# BPSensor_Board.net
KiCad netlist of a schematic drawn in Altium Designer
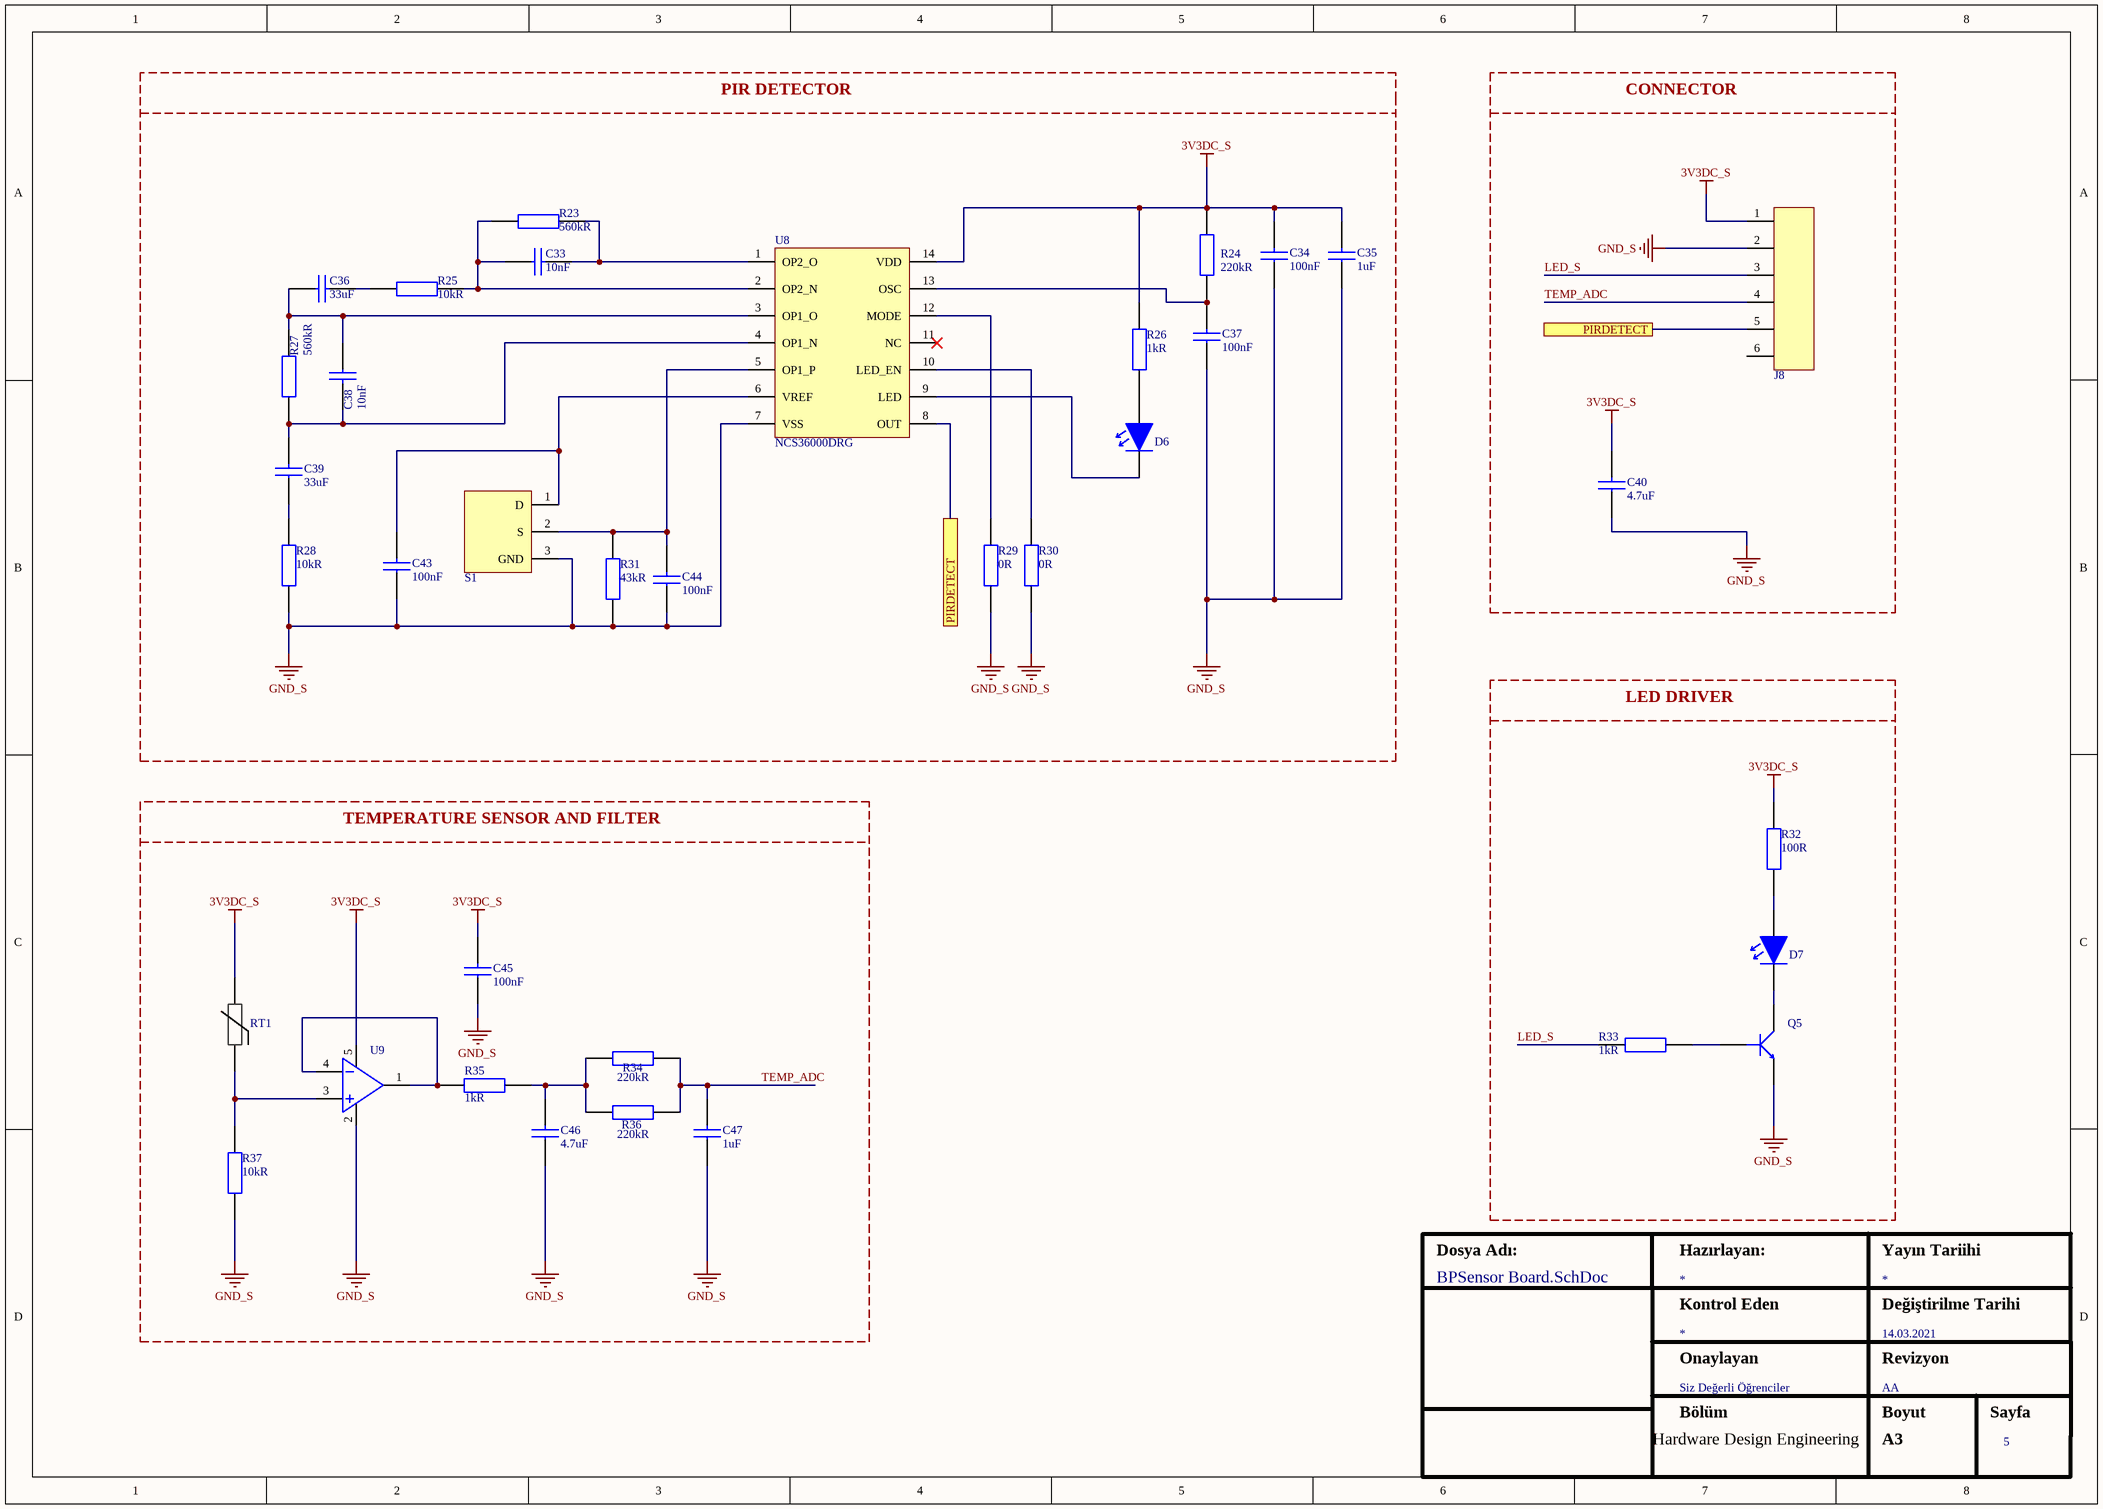
[diagram p0: BPSensor Board.SchDoc]

(export (version "E")
  (design (tool "Eeschema 10.0.6"))
  (components
    (comp (ref "C33")
      (value "0603B103K160CT")
      (footprint "CAP_0603")
      (description "CAP CER 10nF %10 0603")
      (fields
        (field (name "MANUFACTURER") "Walsin Technologies")
        (field (name "TOLERANCE") "10%")
        (field (name "CAPACITANCE") "10nF")
        (field (name "DESIGNED BY") "BERK")
      )
      (libsource (lib "UDEMY_Library") (part "CAP CER 10nF 0603"))
    )
    (comp (ref "C34")
      (value "C0603C104K5RACTU")
      (footprint "CAP_0603")
      (description "CAP CER 100nF %10 0603 SMD")
      (fields
        (field (name "MANUFACTURER") "KEMET")
        (field (name "TOLERANCE") "10%")
        (field (name "CAPACITANCE") "100nF")
        (field (name "DESIGNED BY") "BERK")
      )
      (libsource (lib "UDEMY_Library") (part "CAP CER 100nF 0603"))
    )
    (comp (ref "C35")
      (value "CL21B105KBFNNNE")
      (footprint "CAP_0805")
      (description "CAP CER 1uF %10 0805")
      (fields
        (field (name "MANUFACTURER") "Samsung")
        (field (name "TOLERANCE") "10%")
        (field (name "CAPACITANCE") "1uF")
        (field (name "DESIGNED BY") "BERK")
      )
      (libsource (lib "UDEMY_Library") (part "CAP CER 1uF 0805"))
    )
    (comp (ref "C36")
      (value "C3216X5R1E336M160AC")
      (footprint "CAP_1206")
      (description "CAP CER 33uF %20 1206 SMD")
      (fields
        (field (name "MANUFACTURER") "TDK")
        (field (name "TOLERANCE") "20%")
        (field (name "CAPACITANCE") "33uF")
        (field (name "DESIGNED BY") "BERK")
      )
      (libsource (lib "UDEMY_Library") (part "CAP CER 33uF 1206"))
    )
    (comp (ref "C37")
      (value "C0603C104K5RACTU")
      (footprint "CAP_0603")
      (description "CAP CER 100nF %10 0603 SMD")
      (fields
        (field (name "MANUFACTURER") "KEMET")
        (field (name "TOLERANCE") "10%")
        (field (name "CAPACITANCE") "100nF")
        (field (name "DESIGNED BY") "BERK")
      )
      (libsource (lib "UDEMY_Library") (part "CAP CER 100nF 0603"))
    )
    (comp (ref "C38")
      (value "0603B103K160CT")
      (footprint "CAP_0603")
      (description "CAP CER 10nF %10 0603")
      (fields
        (field (name "MANUFACTURER") "Walsin Technologies")
        (field (name "TOLERANCE") "10%")
        (field (name "CAPACITANCE") "10nF")
        (field (name "DESIGNED BY") "BERK")
      )
      (libsource (lib "UDEMY_Library") (part "CAP CER 10nF 0603"))
    )
    (comp (ref "C39")
      (value "C3216X5R1E336M160AC")
      (footprint "CAP_1206")
      (description "CAP CER 33uF %20 1206 SMD")
      (fields
        (field (name "MANUFACTURER") "TDK")
        (field (name "TOLERANCE") "20%")
        (field (name "CAPACITANCE") "33uF")
        (field (name "DESIGNED BY") "BERK")
      )
      (libsource (lib "UDEMY_Library") (part "CAP CER 33uF 1206"))
    )
    (comp (ref "C40")
      (value "CL21A475KAQNNNE")
      (footprint "CAP_0805")
      (description "CAP CER 4.7uF %10 0805")
      (fields
        (field (name "MANUFACTURER") "Samsung")
        (field (name "TOLERANCE") "10%")
        (field (name "CAPACITANCE") "4.7uF")
        (field (name "DESIGNED BY") "BERK")
      )
      (libsource (lib "UDEMY_Library") (part "CAP CER 4.7uF 0805"))
    )
    (comp (ref "C43")
      (value "C0603C104K5RACTU")
      (footprint "CAP_0603")
      (description "CAP CER 100nF %10 0603 SMD")
      (fields
        (field (name "MANUFACTURER") "KEMET")
        (field (name "TOLERANCE") "10%")
        (field (name "CAPACITANCE") "100nF")
        (field (name "DESIGNED BY") "BERK")
      )
      (libsource (lib "UDEMY_Library") (part "CAP CER 100nF 0603"))
    )
    (comp (ref "C44")
      (value "C0603C104K5RACTU")
      (footprint "CAP_0603")
      (description "CAP CER 100nF %10 0603 SMD")
      (fields
        (field (name "MANUFACTURER") "KEMET")
        (field (name "TOLERANCE") "10%")
        (field (name "CAPACITANCE") "100nF")
        (field (name "DESIGNED BY") "BERK")
      )
      (libsource (lib "UDEMY_Library") (part "CAP CER 100nF 0603"))
    )
    (comp (ref "C45")
      (value "C0603C104K5RACTU")
      (footprint "CAP_0603")
      (description "CAP CER 100nF %10 0603 SMD")
      (fields
        (field (name "MANUFACTURER") "KEMET")
        (field (name "TOLERANCE") "10%")
        (field (name "CAPACITANCE") "100nF")
        (field (name "DESIGNED BY") "BERK")
      )
      (libsource (lib "UDEMY_Library") (part "CAP CER 100nF 0603"))
    )
    (comp (ref "C46")
      (value "CL21A475KAQNNNE")
      (footprint "CAP_0805")
      (description "CAP CER 4.7uF %10 0805")
      (fields
        (field (name "MANUFACTURER") "Samsung")
        (field (name "TOLERANCE") "10%")
        (field (name "CAPACITANCE") "4.7uF")
        (field (name "DESIGNED BY") "BERK")
      )
      (libsource (lib "UDEMY_Library") (part "CAP CER 4.7uF 0805"))
    )
    (comp (ref "C47")
      (value "CL21B105KBFNNNE")
      (footprint "CAP_0805")
      (description "CAP CER 1uF %10 0805")
      (fields
        (field (name "MANUFACTURER") "Samsung")
        (field (name "TOLERANCE") "10%")
        (field (name "CAPACITANCE") "1uF")
        (field (name "DESIGNED BY") "BERK")
      )
      (libsource (lib "UDEMY_Library") (part "CAP CER 1uF 0805"))
    )
    (comp (ref "D6")
      (value "LTST-C171GKT")
      (footprint "LED_GREEN_0805")
      (description "Green 0805 130 º Min 5 mcd Typical 12 mcd Water Clear Lens SMT LED")
      (fields (field (name "MANUFACTURER") "Vishay Lite-On") (field (name "DESIGNED BY") "BERK"))
      (libsource (lib "UDEMY_Library") (part "LED GREEN 0805"))
    )
    (comp (ref "D7")
      (value "LH R974-LP-1")
      (footprint "LED_RED_0805")
      (description "LED Uni-Color Hyper Red 660nm 2-Pin Chip 0805(2012Metric) T/R")
      (fields (field (name "MANUFACTURER") "Osram Opto") (field (name "DESIGNED BY") "BERK"))
      (libsource (lib "UDEMY_Library") (part "LED RED 0805"))
    )
    (comp (ref "J8")
      (value "64800611622")
      (footprint "BPSchematic:64800611622")
      (description "1.50mm 6PIN Connector")
      (fields (field (name "MANUFACTURER") "Wurth Electronics"))
      (libsource (lib "UDEMY_Library") (part "64800611622_conn_6pin"))
    )
    (comp (ref "Q5")
      (value "MMBT3904-7-F")
      (footprint "SOT-23F")
      (description "Transistor General Purpose BJT NPN 40 Volt 0.2A Automotive 3-Pin SOT-23")
      (fields (field (name "MANUFACTURER") "Diodes Zetex") (field (name "DESIGNED BY") "BERK"))
      (libsource (lib "UDEMY_Library") (part "MMBT3904-7-F"))
    )
    (comp (ref "R23")
      (value "RC0603JR-07560KL")
      (footprint "RES_0603")
      (description "RES SMD 560K OHM 5% 1/10W 0603")
      (fields
        (field (name "MANUFACTURER") "Yageo")
        (field (name "TOLERANCE") "5%")
        (field (name "RESISTANCE") "560kR")
        (field (name "DESIGNED BY") "BERK")
      )
      (libsource (lib "") (part "RES 560K OHM 0603_1"))
    )
    (comp (ref "R24")
      (value "RC0603JR-07220KL")
      (footprint "RES_0603")
      (description "RES 220K %5 OHM 0603 SMD")
      (fields
        (field (name "MANUFACTURER") "Yageo")
        (field (name "TOLERANCE") "5%")
        (field (name "RESISTANCE") "220kR")
      )
      (libsource (lib "") (part "RES 220K OHM 0603_1"))
    )
    (comp (ref "R25")
      (value "RC0603FR-0710KL")
      (footprint "RES_0603")
      (description "RES 10K %1 OHM 0603 SMD")
      (fields
        (field (name "MANUFACTURER") "Yageo")
        (field (name "TOLERANCE") "1%")
        (field (name "RESISTANCE") "10kR")
        (field (name "DESIGNED BY") "BERK")
      )
      (libsource (lib "UDEMY_Library") (part "RES 10K OHM 0603"))
    )
    (comp (ref "R26")
      (value "RC0603FR-0710KL")
      (footprint "RES_0603")
      (description "RES 1K %1 OHM 0603 SMD")
      (fields
        (field (name "MANUFACTURER") "Yageo")
        (field (name "MANUFACTURER PART NUMBER") "RC0603JR-071KL")
        (field (name "RESISTANCE") "1kR")
        (field (name "DESIGNED BY") "BERK")
      )
      (libsource (lib "") (part "RES 1K OHM 0603_1"))
    )
    (comp (ref "R27")
      (value "RC0603JR-07560KL")
      (footprint "RES_0603")
      (description "RES SMD 560K OHM 5% 1/10W 0603")
      (fields
        (field (name "MANUFACTURER") "Yageo")
        (field (name "TOLERANCE") "5%")
        (field (name "RESISTANCE") "560kR")
        (field (name "DESIGNED BY") "BERK")
      )
      (libsource (lib "UDEMY_Library") (part "RES 560K OHM 0603"))
    )
    (comp (ref "R28")
      (value "RC0603FR-0710KL")
      (footprint "RES_0603")
      (description "RES 10K %1 OHM 0603 SMD")
      (fields
        (field (name "MANUFACTURER") "Yageo")
        (field (name "TOLERANCE") "1%")
        (field (name "RESISTANCE") "10kR")
        (field (name "DESIGNED BY") "BERK")
      )
      (libsource (lib "") (part "RES 10K OHM 0603_1"))
    )
    (comp (ref "R29")
      (value "RC0603JR-070RL")
      (footprint "RES_0603")
      (description "RES 0 %1 OHM 0603 SMD")
      (fields
        (field (name "MANUFACTURER") "Yageo")
        (field (name "TOLERANCE") "1%")
        (field (name "RESISTANCE") "0R")
        (field (name "DESIGNED BY") "BERK")
      )
      (libsource (lib "UDEMY_Library") (part "RES 0 OHM 0603"))
    )
    (comp (ref "R30")
      (value "RC0603JR-070RL")
      (footprint "RES_0603")
      (description "RES 0 %1 OHM 0603 SMD")
      (fields
        (field (name "MANUFACTURER") "Yageo")
        (field (name "TOLERANCE") "1%")
        (field (name "RESISTANCE") "0R")
        (field (name "DESIGNED BY") "BERK")
      )
      (libsource (lib "UDEMY_Library") (part "RES 0 OHM 0603"))
    )
    (comp (ref "R31")
      (value "RC0603JR-0743KL")
      (footprint "RES_0603")
      (description "RES 43K %5 OHM 0603 SMD")
      (fields
        (field (name "MANUFACTURER") "Yageo")
        (field (name "TOLERANCE") "5%")
        (field (name "RESISTANCE") "43kR")
        (field (name "DESIGNED BY") "BERK")
      )
      (libsource (lib "UDEMY_Library") (part "RES 43K OHM 0603"))
    )
    (comp (ref "R32")
      (value "RC0603JR-07100RL")
      (footprint "RES_0603")
      (description "RES 100 %5 OHM 0603 SMD")
      (fields
        (field (name "MANUFACTURER") "Yageo")
        (field (name "TOLERANCE") "5%")
        (field (name "RESISTANCE") "100R")
        (field (name "DESIGNED BY") "BERK")
      )
      (libsource (lib "UDEMY_Library") (part "RES 100 OHM 0603"))
    )
    (comp (ref "R33")
      (value "RC0603FR-0710KL")
      (footprint "RES_0603")
      (description "RES 1K %1 OHM 0603 SMD")
      (fields
        (field (name "MANUFACTURER") "Yageo")
        (field (name "MANUFACTURER PART NUMBER") "RC0603JR-071KL")
        (field (name "RESISTANCE") "1kR")
        (field (name "DESIGNED BY") "BERK")
      )
      (libsource (lib "UDEMY_Library") (part "RES 1K OHM 0603"))
    )
    (comp (ref "R34")
      (value "RC0603JR-07220KL")
      (footprint "RES_0603")
      (description "RES 220K %5 OHM 0603 SMD")
      (fields
        (field (name "MANUFACTURER") "Yageo")
        (field (name "TOLERANCE") "5%")
        (field (name "RESISTANCE") "220kR")
      )
      (libsource (lib "UDEMY_Library") (part "RES 220K OHM 0603"))
    )
    (comp (ref "R35")
      (value "RC0603FR-0710KL")
      (footprint "RES_0603")
      (description "RES 1K %1 OHM 0603 SMD")
      (fields
        (field (name "MANUFACTURER") "Yageo")
        (field (name "MANUFACTURER PART NUMBER") "RC0603JR-071KL")
        (field (name "RESISTANCE") "1kR")
        (field (name "DESIGNED BY") "BERK")
      )
      (libsource (lib "UDEMY_Library") (part "RES 1K OHM 0603"))
    )
    (comp (ref "R36")
      (value "RC0603JR-07220KL")
      (footprint "RES_0603")
      (description "RES 220K %5 OHM 0603 SMD")
      (fields
        (field (name "MANUFACTURER") "Yageo")
        (field (name "TOLERANCE") "5%")
        (field (name "RESISTANCE") "220kR")
      )
      (libsource (lib "UDEMY_Library") (part "RES 220K OHM 0603"))
    )
    (comp (ref "R37")
      (value "RC0603FR-0710KL")
      (footprint "RES_0603")
      (description "RES 10K %1 OHM 0603 SMD")
      (fields
        (field (name "MANUFACTURER") "Yageo")
        (field (name "TOLERANCE") "1%")
        (field (name "RESISTANCE") "10kR")
        (field (name "DESIGNED BY") "BERK")
      )
      (libsource (lib "") (part "RES 10K OHM 0603_1"))
    )
    (comp (ref "RT1")
      (value "TFPT1206L1002FM")
      (footprint "RES_1206")
      (description "Thermistor PTC 10K Ohm 1% 1206")
      (fields
        (field (name "MANUFACTURER") "Vishay Dale")
        (field (name "TOLERANCE") "1%")
        (field (name "DESIGNED BY") "BERK")
      )
      (libsource (lib "UDEMY_Library") (part "TFPT1206L1002FM"))
    )
    (comp (ref "S1")
      (value "LHI 878/3902")
      (footprint "LHI 878")
      (description "SENSOR PYRO DETECTOR DUAL MOTION")
      (fields (field (name "DESIGNED BY") "BERK"))
      (libsource (lib "UDEMY_Library") (part "LHI 878/3902"))
    )
    (comp (ref "U8")
      (value "NCS36000DRG")
      (footprint "SOIC14")
      (description "PIR Controller Low Noise Amplifiers and LDO Regulator 14-Pin SOIC N T/R")
      (fields (field (name "MANUFACTURER") "ON Semiconductor") (field (name "DESIGNED BY") "BERK"))
      (libsource (lib "UDEMY_Library") (part "NCS36000"))
    )
    (comp (ref "U9")
      (value "OPA314AIDBVR")
      (footprint "SOT23-5")
      (description "Op Amp OPA314")
      (fields (field (name "MANUFACTURER") "Texas Instruments") (field (name "DESIGNED BY") "BERK"))
      (libsource (lib "UDEMY_Library") (part "OPA314"))
    )
  )
  (nets
    (net (code "1") (name "/LED_S") (class "Default")
      (node (ref "J8") (pin "3") (pintype "power_in"))
      (node (ref "R33") (pin "1") (pinfunction "1_1") (pintype "passive"))
    )
    (net (code "2") (name "/PIRDETECT") (class "Default")
      (node (ref "J8") (pin "5") (pintype "power_in"))
      (node (ref "U8") (pin "8") (pinfunction "OUT_8") (pintype "passive"))
    )
    (net (code "3") (name "/TEMP_ADC") (class "Default")
      (node (ref "C47") (pin "2") (pinfunction "2_2") (pintype "passive"))
      (node (ref "J8") (pin "4") (pintype "power_in"))
      (node (ref "R34") (pin "2") (pinfunction "2_2") (pintype "passive"))
      (node (ref "R36") (pin "2") (pinfunction "2_2") (pintype "passive"))
    )
    (net (code "4") (name "3V3DC_S") (class "Default")
      (node (ref "C34") (pin "2") (pinfunction "2_2") (pintype "passive"))
      (node (ref "C35") (pin "2") (pinfunction "2_2") (pintype "passive"))
      (node (ref "C40") (pin "2") (pinfunction "2_2") (pintype "passive"))
      (node (ref "C45") (pin "2") (pinfunction "2_2") (pintype "passive"))
      (node (ref "J8") (pin "1") (pintype "power_in"))
      (node (ref "R24") (pin "2") (pinfunction "2_2") (pintype "passive"))
      (node (ref "R26") (pin "2") (pinfunction "2_2") (pintype "passive"))
      (node (ref "R32") (pin "2") (pinfunction "2_2") (pintype "passive"))
      (node (ref "RT1") (pin "2") (pinfunction "2_2") (pintype "passive"))
      (node (ref "U8") (pin "14") (pinfunction "VDD_14") (pintype "passive"))
      (node (ref "U9") (pin "5") (pinfunction "5_5") (pintype "passive"))
    )
    (net (code "5") (name "GND_S") (class "Default")
      (node (ref "C34") (pin "1") (pinfunction "1_1") (pintype "passive"))
      (node (ref "C35") (pin "1") (pinfunction "1_1") (pintype "passive"))
      (node (ref "C37") (pin "1") (pinfunction "1_1") (pintype "passive"))
      (node (ref "C40") (pin "1") (pinfunction "1_1") (pintype "passive"))
      (node (ref "C43") (pin "1") (pinfunction "1_1") (pintype "passive"))
      (node (ref "C44") (pin "1") (pinfunction "1_1") (pintype "passive"))
      (node (ref "C45") (pin "1") (pinfunction "1_1") (pintype "passive"))
      (node (ref "C46") (pin "1") (pinfunction "1_1") (pintype "passive"))
      (node (ref "C47") (pin "1") (pinfunction "1_1") (pintype "passive"))
      (node (ref "J8") (pin "2") (pintype "power_in"))
      (node (ref "Q5") (pin "2") (pinfunction "E_2") (pintype "power_in"))
      (node (ref "R28") (pin "1") (pinfunction "1_1") (pintype "passive"))
      (node (ref "R29") (pin "1") (pinfunction "1_1") (pintype "passive"))
      (node (ref "R30") (pin "1") (pinfunction "1_1") (pintype "passive"))
      (node (ref "R31") (pin "1") (pinfunction "1_1") (pintype "passive"))
      (node (ref "R37") (pin "1") (pinfunction "1_1") (pintype "passive"))
      (node (ref "S1") (pin "3") (pinfunction "GND_3") (pintype "passive"))
      (node (ref "U8") (pin "7") (pinfunction "VSS_7") (pintype "passive"))
      (node (ref "U9") (pin "2") (pinfunction "2_2") (pintype "passive"))
    )
    (net (code "6") (name "Net-(C36-Pad2)") (class "Default")
      (node (ref "C36") (pin "2") (pinfunction "2_2") (pintype "passive"))
      (node (ref "R25") (pin "1") (pinfunction "1_1") (pintype "passive"))
    )
    (net (code "7") (name "Net-(C39-Pad1)") (class "Default")
      (node (ref "C39") (pin "1") (pinfunction "1_1") (pintype "passive"))
      (node (ref "R28") (pin "2") (pinfunction "2_2") (pintype "passive"))
    )
    (net (code "8") (name "Net-(C46-Pad2)") (class "Default")
      (node (ref "C46") (pin "2") (pinfunction "2_2") (pintype "passive"))
      (node (ref "R34") (pin "1") (pinfunction "1_1") (pintype "passive"))
      (node (ref "R35") (pin "2") (pinfunction "2_2") (pintype "passive"))
      (node (ref "R36") (pin "1") (pinfunction "1_1") (pintype "passive"))
    )
    (net (code "9") (name "Net-(D6-Pad2)") (class "Default")
      (node (ref "D6") (pin "2") (pinfunction "2_2") (pintype "power_in"))
      (node (ref "R26") (pin "1") (pinfunction "1_1") (pintype "passive"))
    )
    (net (code "10") (name "Net-(D7-Pad2)") (class "Default")
      (node (ref "D7") (pin "2") (pinfunction "2_2") (pintype "power_in"))
      (node (ref "R32") (pin "1") (pinfunction "1_1") (pintype "passive"))
    )
    (net (code "11") (name "Net-(Q5-B)") (class "Default")
      (node (ref "Q5") (pin "1") (pinfunction "B_1") (pintype "power_in"))
      (node (ref "R33") (pin "2") (pinfunction "2_2") (pintype "passive"))
    )
    (net (code "12") (name "Net-(Q5-C)") (class "Default")
      (node (ref "D7") (pin "1") (pinfunction "1_1") (pintype "power_in"))
      (node (ref "Q5") (pin "3") (pinfunction "C_3") (pintype "power_in"))
    )
    (net (code "13") (name "Net-(R35-Pad1)") (class "Default")
      (node (ref "R35") (pin "1") (pinfunction "1_1") (pintype "passive"))
      (node (ref "U9") (pin "1") (pinfunction "1_1") (pintype "passive"))
      (node (ref "U9") (pin "4") (pinfunction "4_4") (pintype "passive"))
    )
    (net (code "14") (name "Net-(R37-Pad2)") (class "Default")
      (node (ref "R37") (pin "2") (pinfunction "2_2") (pintype "passive"))
      (node (ref "RT1") (pin "1") (pinfunction "1_1") (pintype "passive"))
      (node (ref "U9") (pin "3") (pinfunction "3_3") (pintype "passive"))
    )
    (net (code "15") (name "Net-(S1-D)") (class "Default")
      (node (ref "C43") (pin "2") (pinfunction "2_2") (pintype "passive"))
      (node (ref "S1") (pin "1") (pinfunction "D_1") (pintype "passive"))
      (node (ref "U8") (pin "6") (pinfunction "VREF_6") (pintype "passive"))
    )
    (net (code "16") (name "Net-(S1-S)") (class "Default")
      (node (ref "C44") (pin "2") (pinfunction "2_2") (pintype "passive"))
      (node (ref "R31") (pin "2") (pinfunction "2_2") (pintype "passive"))
      (node (ref "S1") (pin "2") (pinfunction "S_2") (pintype "passive"))
      (node (ref "U8") (pin "5") (pinfunction "OP1_P_5") (pintype "passive"))
    )
    (net (code "17") (name "Net-(U8-LED)") (class "Default")
      (node (ref "D6") (pin "1") (pinfunction "1_1") (pintype "power_in"))
      (node (ref "U8") (pin "9") (pinfunction "LED_9") (pintype "passive"))
    )
    (net (code "18") (name "Net-(U8-LED_EN)") (class "Default")
      (node (ref "R30") (pin "2") (pinfunction "2_2") (pintype "passive"))
      (node (ref "U8") (pin "10") (pinfunction "LED_EN_10") (pintype "passive"))
    )
    (net (code "19") (name "Net-(U8-MODE)") (class "Default")
      (node (ref "R29") (pin "2") (pinfunction "2_2") (pintype "passive"))
      (node (ref "U8") (pin "12") (pinfunction "MODE_12") (pintype "passive"))
    )
    (net (code "20") (name "Net-(U8-OP1_N)") (class "Default")
      (node (ref "C38") (pin "2") (pinfunction "2_2") (pintype "passive"))
      (node (ref "C39") (pin "2") (pinfunction "2_2") (pintype "passive"))
      (node (ref "R27") (pin "1") (pinfunction "1_1") (pintype "passive"))
      (node (ref "U8") (pin "4") (pinfunction "OP1_N_4") (pintype "passive"))
    )
    (net (code "21") (name "Net-(U8-OP1_O)") (class "Default")
      (node (ref "C36") (pin "1") (pinfunction "1_1") (pintype "passive"))
      (node (ref "C38") (pin "1") (pinfunction "1_1") (pintype "passive"))
      (node (ref "R27") (pin "2") (pinfunction "2_2") (pintype "passive"))
      (node (ref "U8") (pin "3") (pinfunction "OP1_O_3") (pintype "passive"))
    )
    (net (code "22") (name "Net-(U8-OP2_N)") (class "Default")
      (node (ref "C33") (pin "1") (pinfunction "1_1") (pintype "passive"))
      (node (ref "R23") (pin "1") (pinfunction "1_1") (pintype "passive"))
      (node (ref "R25") (pin "2") (pinfunction "2_2") (pintype "passive"))
      (node (ref "U8") (pin "2") (pinfunction "OP2_N_2") (pintype "passive"))
    )
    (net (code "23") (name "Net-(U8-OP2_O)") (class "Default")
      (node (ref "C33") (pin "2") (pinfunction "2_2") (pintype "passive"))
      (node (ref "R23") (pin "2") (pinfunction "2_2") (pintype "passive"))
      (node (ref "U8") (pin "1") (pinfunction "OP2_O_1") (pintype "passive"))
    )
    (net (code "24") (name "Net-(U8-OSC)") (class "Default")
      (node (ref "C37") (pin "2") (pinfunction "2_2") (pintype "passive"))
      (node (ref "R24") (pin "1") (pinfunction "1_1") (pintype "passive"))
      (node (ref "U8") (pin "13") (pinfunction "OSC_13") (pintype "passive"))
    )
    (net (code "25") (name "unconnected-(J8-Pad6)") (class "Default")
      (node (ref "J8") (pin "6") (pintype "power_in"))
    )
    (net (code "26") (name "unconnected-(U8-NC-Pad11)") (class "Default")
      (node (ref "U8") (pin "11") (pinfunction "NC_11") (pintype "passive+no_connect"))
    )
  )
)
